# rx_path.net
KiCad netlist of a schematic drawn in Altium Designer
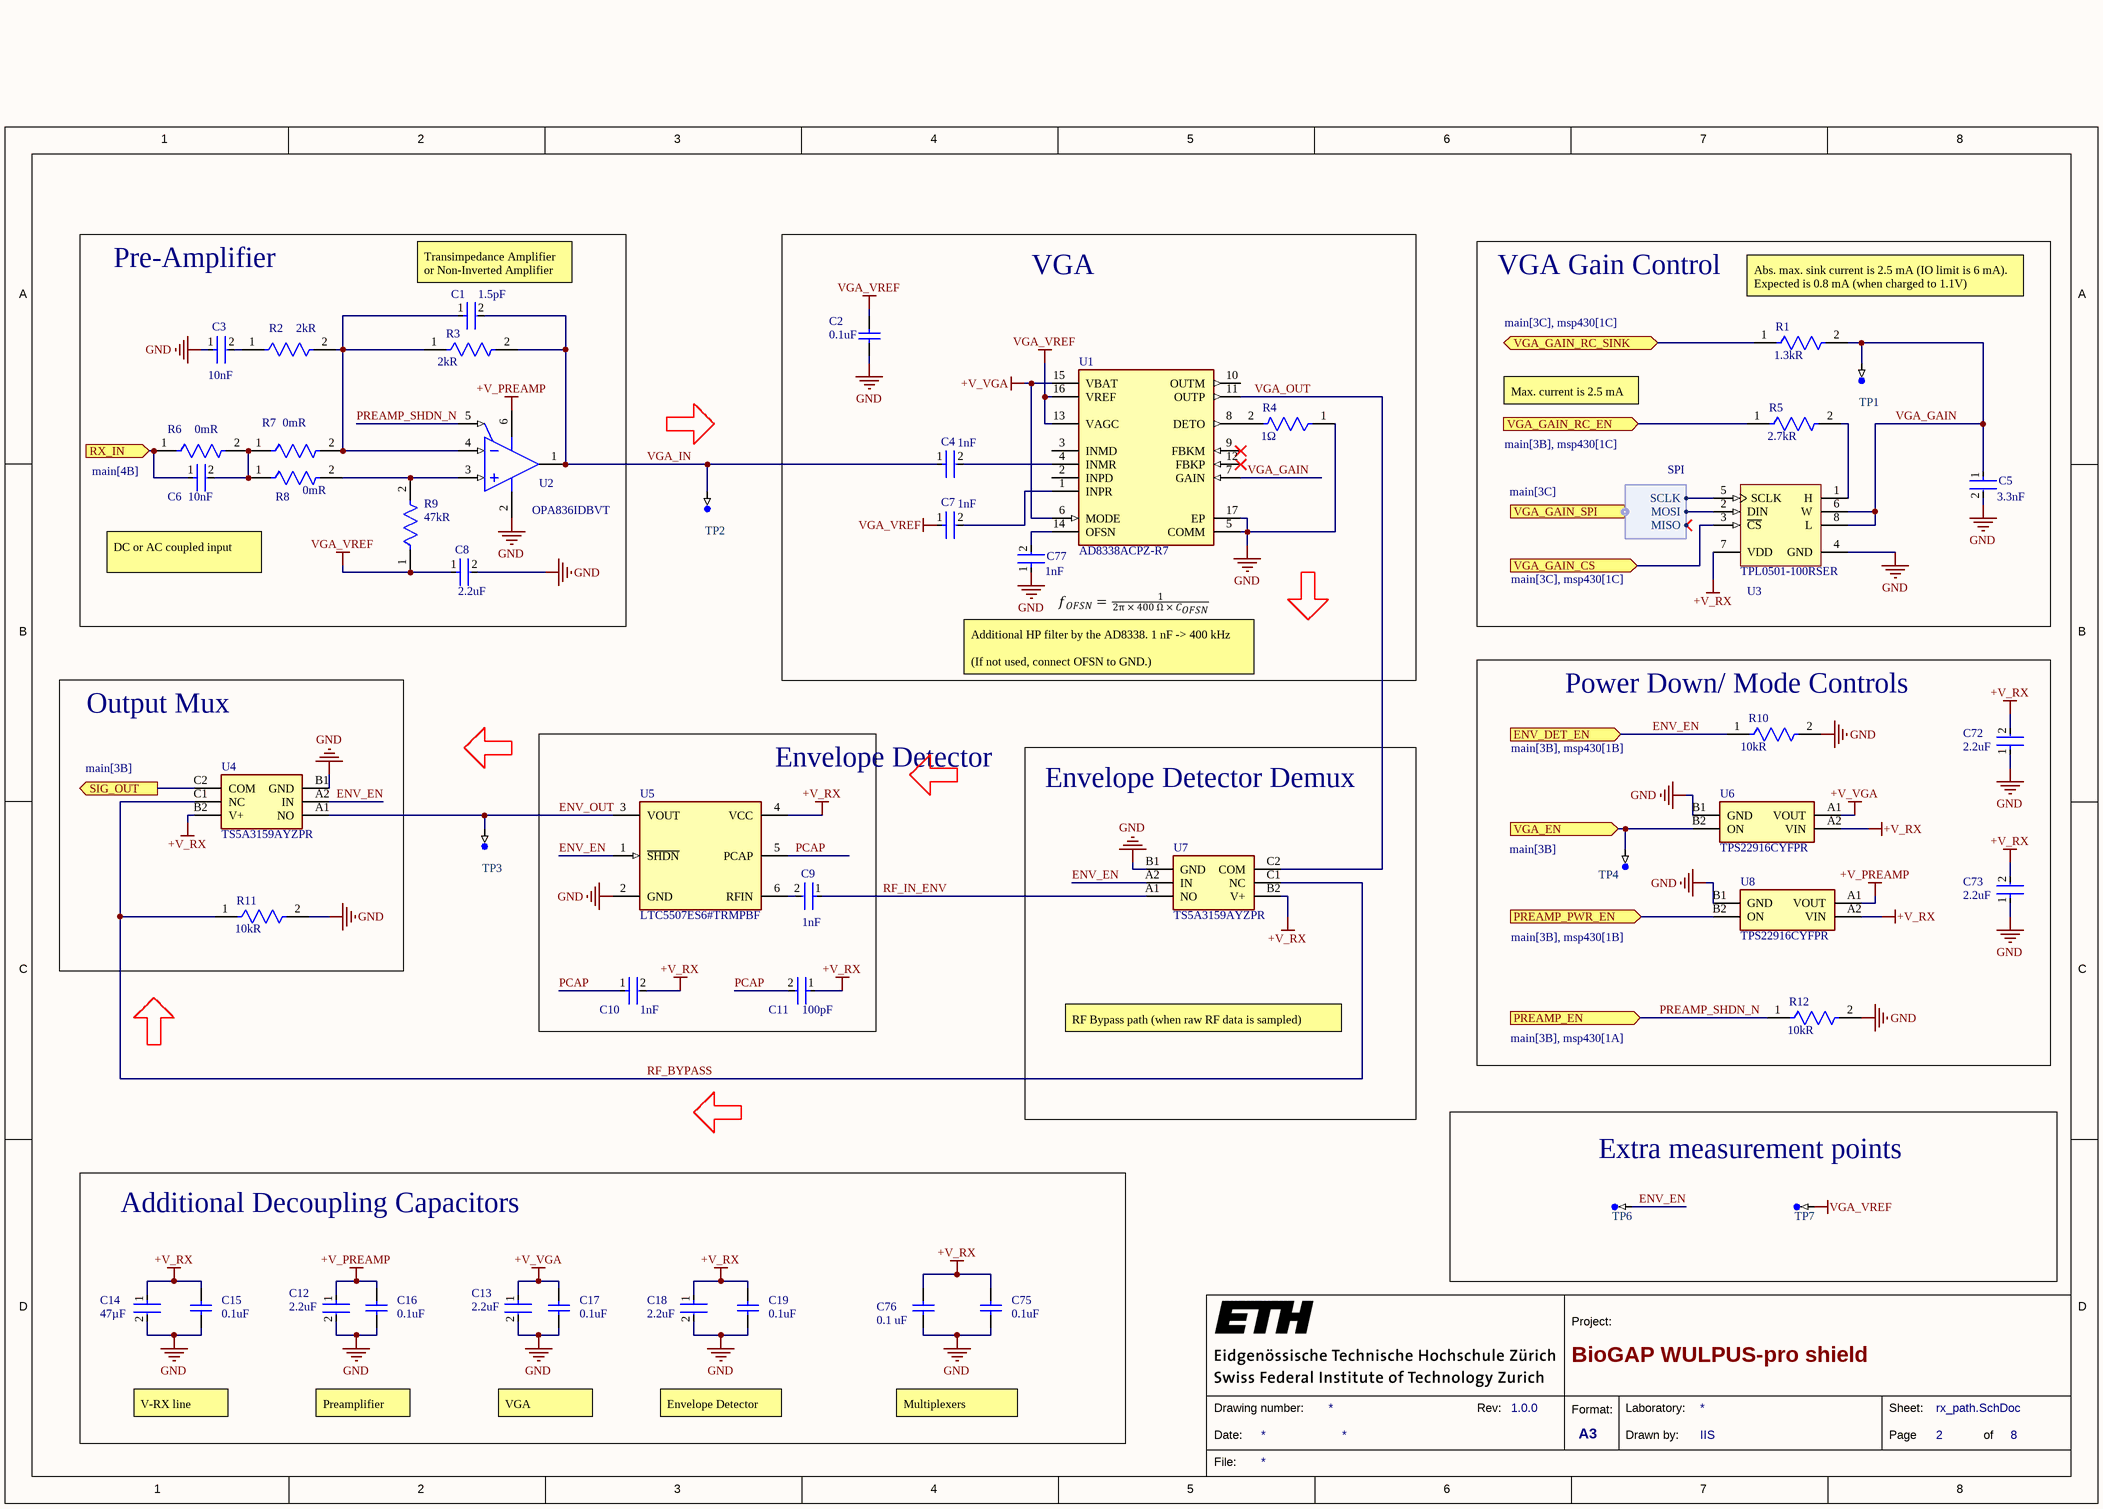
[diagram p0: rx_path.SchDoc]

(export (version "E")
  (design (tool "Eeschema 10.0.6"))
  (components
    (comp (ref "C1")
      (value "GJM1555C1H1R5BB01D")
      (footprint "FP-GJM155-0_05-IPC_C")
      (fields (field (name "CAPACITANCE") "1.5pF") (field (name "VOLTAGE") "50V"))
      (libsource (lib "Altium Content Vault") (part "02cd4be3c70576c341d710602a673aa"))
    )
    (comp (ref "C2")
      (value "C0402C104K4RACTU")
      (footprint "CAPC1005X55X30LL05T10")
      (fields (field (name "MANUFACTURER") "Kemet") (field (name "CAPACITANCE") "0.1uF"))
      (libsource (lib "Altium Content Vault") (part "CAP"))
    )
    (comp (ref "C3")
      (value "GRM033R71A103KA01D")
      (footprint "FP-GRM033-0_03-IPC_B")
      (fields
        (field (name "VOLTAGE") "10V")
        (field (name "CAPACITANCE") "10nF")
        (field (name "TOLERANCE") "10%")
      )
      (libsource (lib "Altium Content Vault") (part "b4654b650e69147ec39a6b967a45e02"))
    )
    (comp (ref "C4")
      (value "GRM1555C1H102JA01D")
      (footprint "FP-GRM155-0_05-IPC_B")
      (fields
        (field (name "TOLERANCE") "5%")
        (field (name "VOLTAGE") "50V")
        (field (name "CAPACITANCE") "1nF")
      )
      (libsource (lib "Altium Content Vault") (part "02cd4be3c70576c341d710602a673aa"))
    )
    (comp (ref "C5")
      (value "04025C332JAT2A")
      (footprint "FP-0402-L_1_0_1-W_0_5_0_1-IPC_C")
      (fields (field (name "CAPACITANCE") "3.3nF") (field (name "TOLERANCE") "5%"))
      (libsource (lib "Altium Content Vault") (part "b4654b650e69147ec39a6b967a45e02"))
    )
    (comp (ref "C6")
      (value "GRM033R71A103KA01D")
      (footprint "FP-GRM033-0_03-IPC_B")
      (fields
        (field (name "VOLTAGE") "10V")
        (field (name "CAPACITANCE") "10nF")
        (field (name "TOLERANCE") "10%")
      )
      (libsource (lib "Altium Content Vault") (part "b4654b650e69147ec39a6b967a45e02"))
    )
    (comp (ref "C7")
      (value "GRM1555C1H102JA01D")
      (footprint "FP-GRM155-0_05-IPC_B")
      (fields
        (field (name "TOLERANCE") "5%")
        (field (name "VOLTAGE") "50V")
        (field (name "CAPACITANCE") "1nF")
      )
      (libsource (lib "Altium Content Vault") (part "02cd4be3c70576c341d710602a673aa"))
    )
    (comp (ref "C8")
      (value "C1005X7S1A225K050BC")
      (footprint "FP-C1005-050-0_15-0_1-MFG")
      (fields (field (name "CAPACITANCE") "2.2uF") (field (name "TOLERANCE") "10%"))
      (libsource (lib "Altium Content Vault") (part "b4654b650e69147ec39a6b967a45e02"))
    )
    (comp (ref "C9")
      (value "GRM1555C1H102JA01D")
      (footprint "FP-GRM155-0_05-IPC_B")
      (fields
        (field (name "TOLERANCE") "5%")
        (field (name "VOLTAGE") "50V")
        (field (name "CAPACITANCE") "1nF")
      )
      (libsource (lib "Altium Content Vault") (part "02cd4be3c70576c341d710602a673aa"))
    )
    (comp (ref "C10")
      (value "GRM1555C1H102JA01D")
      (footprint "FP-GRM155-0_05-IPC_B")
      (fields
        (field (name "TOLERANCE") "5%")
        (field (name "VOLTAGE") "50V")
        (field (name "CAPACITANCE") "1nF")
      )
      (libsource (lib "Altium Content Vault") (part "02cd4be3c70576c341d710602a673aa"))
    )
    (comp (ref "C11")
      (value "04025A101FAT2A")
      (footprint "FP-0402-L_1_0_1-W_0_5_0_1-MFG")
      (fields
        (field (name "CAPACITANCE") "100pF")
        (field (name "VOLTAGE") "50V")
        (field (name "TOLERANCE") "1%")
      )
      (libsource (lib "Altium Content Vault") (part "b4654b650e69147ec39a6b967a45e02"))
    )
    (comp (ref "C12")
      (value "C1005X7S1A225K050BC")
      (footprint "FP-C1005-050-0_15-0_1-MFG")
      (fields (field (name "CAPACITANCE") "2.2uF") (field (name "TOLERANCE") "10%"))
      (libsource (lib "Altium Content Vault") (part "b4654b650e69147ec39a6b967a45e02"))
    )
    (comp (ref "C13")
      (value "C1005X7S1A225K050BC")
      (footprint "FP-C1005-050-0_15-0_1-MFG")
      (fields (field (name "CAPACITANCE") "2.2uF") (field (name "TOLERANCE") "10%"))
      (libsource (lib "Altium Content Vault") (part "b4654b650e69147ec39a6b967a45e02"))
    )
    (comp (ref "C14")
      (value "GRM188R60J476ME01D")
      (footprint "FP-GRM188-0_2-MFG")
      (fields (field (name "TOLERANCE") "20%") (field (name "CAPACITANCE") "47µF"))
      (libsource (lib "Altium Content Vault") (part "b4654b650e69147ec39a6b967a45e02"))
    )
    (comp (ref "C15")
      (value "C0402C104K4RACTU")
      (footprint "CAPC1005X55X30LL05T10")
      (fields (field (name "MANUFACTURER") "Kemet") (field (name "CAPACITANCE") "0.1uF"))
      (libsource (lib "Altium Content Vault") (part "CAP"))
    )
    (comp (ref "C16")
      (value "C0402C104K4RACTU")
      (footprint "CAPC1005X55X30LL05T10")
      (fields (field (name "MANUFACTURER") "Kemet") (field (name "CAPACITANCE") "0.1uF"))
      (libsource (lib "Altium Content Vault") (part "CAP"))
    )
    (comp (ref "C17")
      (value "C0402C104K4RACTU")
      (footprint "CAPC1005X55X30LL05T10")
      (fields (field (name "MANUFACTURER") "Kemet") (field (name "CAPACITANCE") "0.1uF"))
      (libsource (lib "Altium Content Vault") (part "CAP"))
    )
    (comp (ref "C18")
      (value "C1005X7S1A225K050BC")
      (footprint "FP-C1005-050-0_15-0_1-MFG")
      (fields (field (name "CAPACITANCE") "2.2uF") (field (name "TOLERANCE") "10%"))
      (libsource (lib "Altium Content Vault") (part "b4654b650e69147ec39a6b967a45e02"))
    )
    (comp (ref "C19")
      (value "C0402C104K4RACTU")
      (footprint "CAPC1005X55X30LL05T10")
      (fields (field (name "MANUFACTURER") "Kemet") (field (name "CAPACITANCE") "0.1uF"))
      (libsource (lib "Altium Content Vault") (part "CAP"))
    )
    (comp (ref "C72")
      (value "C1005X7S1A225K050BC")
      (footprint "FP-C1005-050-0_15-0_1-MFG")
      (fields (field (name "CAPACITANCE") "2.2uF") (field (name "TOLERANCE") "10%"))
      (libsource (lib "Altium Content Vault") (part "b4654b650e69147ec39a6b967a45e02"))
    )
    (comp (ref "C73")
      (value "C1005X7S1A225K050BC")
      (footprint "FP-C1005-050-0_15-0_1-MFG")
      (fields (field (name "CAPACITANCE") "2.2uF") (field (name "TOLERANCE") "10%"))
      (libsource (lib "Altium Content Vault") (part "b4654b650e69147ec39a6b967a45e02"))
    )
    (comp (ref "C75")
      (value "C0402C104K4RACTU")
      (footprint "CAPC1005X55X30LL05T10")
      (fields (field (name "MANUFACTURER") "Kemet") (field (name "CAPACITANCE") "0.1uF"))
      (libsource (lib "Altium Content Vault") (part "CAP"))
    )
    (comp (ref "C76")
      (value "C0402C104K4RACTU")
      (footprint "CAPC1005X55X30LL05T10")
      (fields (field (name "MANUFACTURER") "Kemet") (field (name "CAPACITANCE") "0.1 uF"))
      (libsource (lib "Altium Content Vault") (part "CAP"))
    )
    (comp (ref "C77")
      (value "GRM1555C1H102JA01D")
      (footprint "FP-GRM155-0_05-IPC_B")
      (fields
        (field (name "TOLERANCE") "5%")
        (field (name "VOLTAGE") "50V")
        (field (name "CAPACITANCE") "1nF")
      )
      (libsource (lib "Altium Content Vault") (part "02cd4be3c70576c341d710602a673aa"))
    )
    (comp (ref "R1")
      (value "CRCW04021K30JNED")
      (footprint "FP-CRCW0402-e3-IPC_B")
      (fields (field (name "TOLERANCE") "5%") (field (name "RESISTANCE") "1.3kR"))
      (libsource (lib "Altium Content Vault") (part "1029c3af85768c4190bb7ad29bc67b5"))
    )
    (comp (ref "R2")
      (value "ERJ-2RKF2001X")
      (footprint "FP-ERJ2RK-MFG")
      (fields (field (name "RESISTANCE") "2kR") (field (name "TOLERANCE") "1%"))
      (libsource (lib "Altium Content Vault") (part "1029c3af85768c4190bb7ad29bc67b5"))
    )
    (comp (ref "R3")
      (value "ERJ-2RKF2001X")
      (footprint "FP-ERJ2RK-MFG")
      (fields (field (name "RESISTANCE") "2kR") (field (name "TOLERANCE") "1%"))
      (libsource (lib "Altium Content Vault") (part "1029c3af85768c4190bb7ad29bc67b5"))
    )
    (comp (ref "R4")
      (value "CRCW04021R00FKEDC")
      (footprint "FP-CRCW0402-C-e3-MFG")
      (fields (field (name "RESISTANCE") "1Ω") (field (name "TOLERANCE") "1%"))
      (libsource (lib "Altium Content Vault") (part "1029c3af85768c4190bb7ad29bc67b5"))
    )
    (comp (ref "R5")
      (value "MCS04020C2701FE000")
      (footprint "FP-MCS0402-IPC_B")
      (fields (field (name "RESISTANCE") "2.7kR") (field (name "TOLERANCE") "1%"))
      (libsource (lib "Altium Content Vault") (part "1029c3af85768c4190bb7ad29bc67b5"))
    )
    (comp (ref "R6")
      (value "CRCW04020000Z0ED")
      (footprint "FP-CRCW0402-e3-IPC_C")
      (fields (field (name "TOLERANCE") "5%") (field (name "RESISTANCE") "0mR"))
      (libsource (lib "Altium Content Vault") (part "1029c3af85768c4190bb7ad29bc67b5"))
    )
    (comp (ref "R7")
      (value "CRCW04020000Z0ED")
      (footprint "FP-CRCW0402-e3-IPC_C")
      (fields (field (name "TOLERANCE") "5%") (field (name "RESISTANCE") "0mR"))
      (libsource (lib "Altium Content Vault") (part "1029c3af85768c4190bb7ad29bc67b5"))
    )
    (comp (ref "R8")
      (value "CRCW04020000Z0ED")
      (footprint "FP-CRCW0402-e3-IPC_C")
      (fields (field (name "TOLERANCE") "5%") (field (name "RESISTANCE") "0mR"))
      (libsource (lib "Altium Content Vault") (part "1029c3af85768c4190bb7ad29bc67b5"))
    )
    (comp (ref "R9")
      (value "RMCF0201JT47K0")
      (footprint "FP-RMCF0201-MFG")
      (fields (field (name "RESISTANCE") "47kR") (field (name "TOLERANCE") "5%"))
      (libsource (lib "Altium Content Vault") (part "1029c3af85768c4190bb7ad29bc67b5"))
    )
    (comp (ref "R10")
      (value "CRCW040210K0JNED")
      (footprint "FP-CRCW0402-e3-IPC_B")
      (fields (field (name "RESISTANCE") "10kR") (field (name "TOLERANCE") "5%"))
      (libsource (lib "Altium Content Vault") (part "1029c3af85768c4190bb7ad29bc67b5"))
    )
    (comp (ref "R11")
      (value "CRCW040210K0JNED")
      (footprint "FP-CRCW0402-e3-IPC_B")
      (fields (field (name "RESISTANCE") "10kR") (field (name "TOLERANCE") "5%"))
      (libsource (lib "Altium Content Vault") (part "1029c3af85768c4190bb7ad29bc67b5"))
    )
    (comp (ref "R12")
      (value "CRCW040210K0JNED")
      (footprint "FP-CRCW0402-e3-IPC_B")
      (fields (field (name "RESISTANCE") "10kR") (field (name "TOLERANCE") "5%"))
      (libsource (lib "Altium Content Vault") (part "1029c3af85768c4190bb7ad29bc67b5"))
    )
    (comp (ref "TP1")
      (value "TP-SM-C-100")
      (footprint "TP-SM-C-100")
      (description "Test Point, Surface Mount, Circular, Pad Diameter 1 mm")
      (libsource (lib "wulpus") (part "CMP-0484-00002-1"))
    )
    (comp (ref "TP2")
      (value "TP-SM-C-100")
      (footprint "TP-SM-C-100")
      (description "Test Point, Surface Mount, Circular, Pad Diameter 1 mm")
      (libsource (lib "wulpus") (part "CMP-0484-00002-1"))
    )
    (comp (ref "TP3")
      (value "TP-SM-C-100")
      (footprint "TP-SM-C-100")
      (description "Test Point, Surface Mount, Circular, Pad Diameter 1 mm")
      (libsource (lib "wulpus") (part "CMP-0484-00002-1"))
    )
    (comp (ref "TP4")
      (value "TP-SM-C-100")
      (footprint "TP-SM-C-100")
      (description "Test Point, Surface Mount, Circular, Pad Diameter 1 mm")
      (libsource (lib "wulpus") (part "CMP-0484-00002-1"))
    )
    (comp (ref "TP6")
      (value "TP-SM-C-100")
      (footprint "TP-SM-C-100")
      (description "Test Point, Surface Mount, Circular, Pad Diameter 1 mm")
      (libsource (lib "wulpus") (part "CMP-0484-00002-1"))
    )
    (comp (ref "TP7")
      (value "TP-SM-C-100")
      (footprint "TP-SM-C-100")
      (description "Test Point, Surface Mount, Circular, Pad Diameter 1 mm")
      (libsource (lib "wulpus") (part "CMP-0484-00002-1"))
    )
    (comp (ref "U1")
      (value "AD8338ACPZ-R7")
      (footprint "FP-CP-16-22-IPC_C")
      (description "IC OPAMP VGA 1 CIRCUIT 16LFCSP")
      (fields
        (field (name "OCTOPART") "https://octopart.com/ad8338acpz-r7-analog+devices-21054770")
        (field (name "MANUFACTURER") "Analog Devices")
      )
      (libsource (lib "Altium Content Vault") (part "4ce7887af0b7713ffabab50ab6d8fb3"))
    )
    (comp (ref "U2")
      (value "OPA836IDBVT")
      (footprint "DBV0006A_L")
      (fields (field (name "MANUFACTURER") "Texas Instruments"))
      (libsource (lib "wulpus") (part "CMP-0018-00480-2"))
    )
    (comp (ref "U3")
      (value "TPL0501-100RSER")
      (footprint "TI-RSE8_V")
      (fields (field (name "MANUFACTURER") "Texas Instruments"))
      (libsource (lib "Altium Content Vault") (part "TI-TPL0501-100RSE8"))
    )
    (comp (ref "U4")
      (value "TS5A3159AYZPR")
      (footprint "BGA6C50P2X3_89X139X50")
      (description "Analogue Switch ICs SPDT ANALOG SWITCH")
      (libsource (lib "TS5A3159AYZPR") (part "TS5A3159AYZPR"))
    )
    (comp (ref "U5")
      (value "LTC5507ES6#TRMPBF")
      (footprint "FP-LTC5507ES6#TRMPBF-IPC_B")
      (description "IC RF DETECT 100KHZ-1GHZ TSOT23")
      (fields
        (field (name "OCTOPART") "https://octopart.com/ltc5507es6%23trmpbf-analog+devices-88320008")
        (field (name "MANUFACTURER") "Analog Devices")
      )
      (libsource (lib "Altium Content Vault") (part "942e158bd38935f4e9b1d9ad82e87f8"))
    )
    (comp (ref "U6")
      (value "TPS22916CYFPR")
      (footprint "BGA4C40P2X2_78X78X50")
      (description "TPS22916 5.5-V, 2-A Ultra-Low Leakage Load Switch")
      (libsource (lib "TPS22916CYFPR") (part "TPS22916CYFPR"))
    )
    (comp (ref "U7")
      (value "TS5A3159AYZPR")
      (footprint "BGA6C50P2X3_89X139X50")
      (description "Analogue Switch ICs SPDT ANALOG SWITCH")
      (libsource (lib "") (part "TS5A3159AYZPR_1"))
    )
    (comp (ref "U8")
      (value "TPS22916CYFPR")
      (footprint "BGA4C40P2X2_78X78X50")
      (description "TPS22916 5.5-V, 2-A Ultra-Low Leakage Load Switch")
      (libsource (lib "TPS22916CYFPR") (part "TPS22916CYFPR"))
    )
  )
  (nets
    (net (code "2") (name "+V_PREAMP") (class "Default")
      (node (ref "C12") (pin "1") (pinfunction "1_1") (pintype "passive"))
      (node (ref "C16") (pin "2") (pinfunction "2_2") (pintype "passive"))
      (node (ref "U2") (pin "6") (pinfunction "VS+_6") (pintype "power_in"))
      (node (ref "U8") (pin "A1") (pinfunction "VOUT_A1") (pintype "passive"))
    )
    (net (code "3") (name "+V_RX") (class "Default")
      (node (ref "C10") (pin "2") (pinfunction "2_2") (pintype "passive"))
      (node (ref "C11") (pin "1") (pinfunction "1_1") (pintype "passive"))
      (node (ref "C14") (pin "1") (pinfunction "1_1") (pintype "passive"))
      (node (ref "C15") (pin "2") (pinfunction "2_2") (pintype "passive"))
      (node (ref "C18") (pin "1") (pinfunction "1_1") (pintype "passive"))
      (node (ref "C19") (pin "2") (pinfunction "2_2") (pintype "passive"))
      (node (ref "C72") (pin "2") (pinfunction "2_2") (pintype "passive"))
      (node (ref "C73") (pin "2") (pinfunction "2_2") (pintype "passive"))
      (node (ref "C75") (pin "2") (pinfunction "2_2") (pintype "passive"))
      (node (ref "C76") (pin "2") (pinfunction "2_2") (pintype "passive"))
      (node (ref "U3") (pin "7") (pinfunction "VDD_7") (pintype "power_in"))
      (node (ref "U4") (pin "B2") (pinfunction "V+_B2") (pintype "passive"))
      (node (ref "U5") (pin "4") (pinfunction "VCC_4") (pintype "power_in"))
      (node (ref "U6") (pin "A2") (pinfunction "VIN_A2") (pintype "passive"))
      (node (ref "U7") (pin "B2") (pinfunction "V+_B2") (pintype "passive"))
      (node (ref "U8") (pin "A2") (pinfunction "VIN_A2") (pintype "passive"))
    )
    (net (code "4") (name "+V_VGA") (class "Default")
      (node (ref "C13") (pin "1") (pinfunction "1_1") (pintype "passive"))
      (node (ref "C17") (pin "2") (pinfunction "2_2") (pintype "passive"))
      (node (ref "U1") (pin "15") (pinfunction "VBAT_15") (pintype "power_in"))
      (node (ref "U1") (pin "6") (pinfunction "MODE_6") (pintype "input"))
      (node (ref "U6") (pin "A1") (pinfunction "VOUT_A1") (pintype "passive"))
    )
    (net (code "5") (name "/ENV_EN") (class "Default")
      (node (ref "R10") (pin "1") (pinfunction "1_1") (pintype "passive"))
      (node (ref "TP6") (pin "1") (pinfunction "1_1") (pintype "input"))
      (node (ref "U4") (pin "A2") (pinfunction "IN_A2") (pintype "passive"))
      (node (ref "U5") (pin "1") (pinfunction "~{SHDN}_1") (pintype "input"))
      (node (ref "U7") (pin "A2") (pinfunction "IN_A2") (pintype "passive"))
    )
    (net (code "6") (name "/ENV_OUT") (class "Default")
      (node (ref "TP3") (pin "1") (pinfunction "1_1") (pintype "input"))
      (node (ref "U4") (pin "A1") (pinfunction "NO_A1") (pintype "passive"))
      (node (ref "U5") (pin "3") (pinfunction "VOUT_3") (pintype "passive"))
    )
    (net (code "7") (name "/MOSI") (class "Default")
      (node (ref "U3") (pin "2") (pinfunction "DIN_2") (pintype "input"))
    )
    (net (code "8") (name "/PCAP") (class "Default")
      (node (ref "C10") (pin "1") (pinfunction "1_1") (pintype "passive"))
      (node (ref "C11") (pin "2") (pinfunction "2_2") (pintype "passive"))
      (node (ref "U5") (pin "5") (pinfunction "PCAP_5") (pintype "passive"))
    )
    (net (code "9") (name "/PREAMP_PWR_EN") (class "Default")
      (node (ref "U8") (pin "B2") (pinfunction "ON_B2") (pintype "passive"))
    )
    (net (code "10") (name "/PREAMP_SHDN_N") (class "Default")
      (node (ref "R12") (pin "1") (pinfunction "1_1") (pintype "passive"))
      (node (ref "U2") (pin "5") (pinfunction "~{PD}_5") (pintype "input"))
    )
    (net (code "11") (name "/RF_BYPASS") (class "Default")
      (node (ref "R11") (pin "1") (pinfunction "1_1") (pintype "passive"))
      (node (ref "U4") (pin "C1") (pinfunction "NC_C1") (pintype "passive"))
      (node (ref "U7") (pin "C1") (pinfunction "NC_C1") (pintype "passive"))
    )
    (net (code "12") (name "/RF_IN_ENV") (class "Default")
      (node (ref "C9") (pin "1") (pinfunction "1_1") (pintype "passive"))
      (node (ref "U7") (pin "A1") (pinfunction "NO_A1") (pintype "passive"))
    )
    (net (code "13") (name "/RX_IN") (class "Default")
      (node (ref "C6") (pin "1") (pinfunction "1_1") (pintype "passive"))
      (node (ref "R6") (pin "1") (pinfunction "1_1") (pintype "passive"))
    )
    (net (code "14") (name "/SCLK") (class "Default")
      (node (ref "U3") (pin "5") (pinfunction "SCLK_5") (pintype "input"))
    )
    (net (code "15") (name "/SIG_OUT") (class "Default")
      (node (ref "U4") (pin "C2") (pinfunction "COM_C2") (pintype "passive"))
    )
    (net (code "16") (name "/VGA_EN") (class "Default")
      (node (ref "TP4") (pin "1") (pinfunction "1_1") (pintype "input"))
      (node (ref "U6") (pin "B2") (pinfunction "ON_B2") (pintype "passive"))
    )
    (net (code "17") (name "/VGA_GAIN") (class "Default")
      (node (ref "C5") (pin "1") (pinfunction "1_1") (pintype "passive"))
      (node (ref "R1") (pin "2") (pinfunction "2_2") (pintype "passive"))
      (node (ref "TP1") (pin "1") (pinfunction "1_1") (pintype "input"))
      (node (ref "U1") (pin "7") (pinfunction "GAIN_7") (pintype "input"))
      (node (ref "U3") (pin "6") (pinfunction "W_6") (pintype "passive"))
      (node (ref "U3") (pin "8") (pinfunction "L_8") (pintype "passive"))
    )
    (net (code "18") (name "/VGA_GAIN_CS") (class "Default")
      (node (ref "U3") (pin "3") (pinfunction "~{CS}_3") (pintype "input"))
    )
    (net (code "19") (name "/VGA_GAIN_RC_EN") (class "Default")
      (node (ref "R5") (pin "1") (pinfunction "1_1") (pintype "passive"))
    )
    (net (code "20") (name "/VGA_GAIN_RC_SINK") (class "Default")
      (node (ref "R1") (pin "1") (pinfunction "1_1") (pintype "passive"))
    )
    (net (code "21") (name "/VGA_IN") (class "Default")
      (node (ref "C1") (pin "2") (pinfunction "2_2") (pintype "passive"))
      (node (ref "C4") (pin "1") (pinfunction "1_1") (pintype "passive"))
      (node (ref "R3") (pin "2") (pinfunction "2_2") (pintype "passive"))
      (node (ref "TP2") (pin "1") (pinfunction "1_1") (pintype "input"))
      (node (ref "U2") (pin "1") (pinfunction "VOUT_1") (pintype "tri_state"))
    )
    (net (code "22") (name "/VGA_OUT") (class "Default")
      (node (ref "U1") (pin "11") (pinfunction "OUTP_11") (pintype "output"))
      (node (ref "U7") (pin "C2") (pinfunction "COM_C2") (pintype "passive"))
    )
    (net (code "24") (name "GND") (class "Default")
      (node (ref "C12") (pin "2") (pinfunction "2_2") (pintype "passive"))
      (node (ref "C13") (pin "2") (pinfunction "2_2") (pintype "passive"))
      (node (ref "C14") (pin "2") (pinfunction "2_2") (pintype "passive"))
      (node (ref "C15") (pin "1") (pinfunction "1_1") (pintype "passive"))
      (node (ref "C16") (pin "1") (pinfunction "1_1") (pintype "passive"))
      (node (ref "C17") (pin "1") (pinfunction "1_1") (pintype "passive"))
      (node (ref "C18") (pin "2") (pinfunction "2_2") (pintype "passive"))
      (node (ref "C19") (pin "1") (pinfunction "1_1") (pintype "passive"))
      (node (ref "C2") (pin "1") (pinfunction "1_1") (pintype "passive"))
      (node (ref "C3") (pin "1") (pinfunction "1_1") (pintype "passive"))
      (node (ref "C5") (pin "2") (pinfunction "2_2") (pintype "passive"))
      (node (ref "C72") (pin "1") (pinfunction "1_1") (pintype "passive"))
      (node (ref "C73") (pin "1") (pinfunction "1_1") (pintype "passive"))
      (node (ref "C75") (pin "1") (pinfunction "1_1") (pintype "passive"))
      (node (ref "C76") (pin "1") (pinfunction "1_1") (pintype "passive"))
      (node (ref "C77") (pin "1") (pinfunction "1_1") (pintype "passive"))
      (node (ref "C8") (pin "2") (pinfunction "2_2") (pintype "passive"))
      (node (ref "R10") (pin "2") (pinfunction "2_2") (pintype "passive"))
      (node (ref "R11") (pin "2") (pinfunction "2_2") (pintype "passive"))
      (node (ref "R12") (pin "2") (pinfunction "2_2") (pintype "passive"))
      (node (ref "R4") (pin "1") (pinfunction "1_1") (pintype "passive"))
      (node (ref "U1") (pin "17") (pinfunction "EP_17") (pintype "power_in"))
      (node (ref "U1") (pin "5") (pinfunction "COMM_5") (pintype "power_in"))
      (node (ref "U2") (pin "2") (pinfunction "VS-_2") (pintype "power_in"))
      (node (ref "U3") (pin "4") (pinfunction "GND_4") (pintype "power_in"))
      (node (ref "U4") (pin "B1") (pinfunction "GND_B1") (pintype "passive"))
      (node (ref "U5") (pin "2") (pinfunction "GND_2") (pintype "power_in"))
      (node (ref "U6") (pin "B1") (pinfunction "GND_B1") (pintype "passive"))
      (node (ref "U7") (pin "B1") (pinfunction "GND_B1") (pintype "passive"))
      (node (ref "U8") (pin "B1") (pinfunction "GND_B1") (pintype "passive"))
    )
    (net (code "25") (name "Net-(C3-Pad2)") (class "Default")
      (node (ref "C3") (pin "2") (pinfunction "2_2") (pintype "passive"))
      (node (ref "R2") (pin "1") (pinfunction "1_1") (pintype "passive"))
    )
    (net (code "26") (name "Net-(C6-Pad2)") (class "Default")
      (node (ref "C6") (pin "2") (pinfunction "2_2") (pintype "passive"))
      (node (ref "R6") (pin "2") (pinfunction "2_2") (pintype "passive"))
      (node (ref "R7") (pin "1") (pinfunction "1_1") (pintype "passive"))
      (node (ref "R8") (pin "1") (pinfunction "1_1") (pintype "passive"))
    )
    (net (code "27") (name "Net-(U1-DETO)") (class "Default")
      (node (ref "R4") (pin "2") (pinfunction "2_2") (pintype "passive"))
      (node (ref "U1") (pin "8") (pinfunction "DETO_8") (pintype "output"))
    )
    (net (code "28") (name "Net-(U1-INMR)") (class "Default")
      (node (ref "C4") (pin "2") (pinfunction "2_2") (pintype "passive"))
      (node (ref "U1") (pin "4") (pinfunction "INMR_4") (pintype "passive"))
    )
    (net (code "29") (name "Net-(U1-INPR)") (class "Default")
      (node (ref "C7") (pin "2") (pinfunction "2_2") (pintype "passive"))
      (node (ref "U1") (pin "1") (pinfunction "INPR_1") (pintype "passive"))
    )
    (net (code "30") (name "Net-(U1-OFSN)") (class "Default")
      (node (ref "C77") (pin "2") (pinfunction "2_2") (pintype "passive"))
      (node (ref "U1") (pin "14") (pinfunction "OFSN_14") (pintype "passive"))
    )
    (net (code "31") (name "Net-(U2-VIN+)") (class "Default")
      (node (ref "R8") (pin "2") (pinfunction "2_2") (pintype "passive"))
      (node (ref "R9") (pin "2") (pinfunction "2_2") (pintype "passive"))
      (node (ref "U2") (pin "3") (pinfunction "VIN+_3") (pintype "input"))
    )
    (net (code "32") (name "Net-(U2-VIN-)") (class "Default")
      (node (ref "C1") (pin "1") (pinfunction "1_1") (pintype "passive"))
      (node (ref "R2") (pin "2") (pinfunction "2_2") (pintype "passive"))
      (node (ref "R3") (pin "1") (pinfunction "1_1") (pintype "passive"))
      (node (ref "R7") (pin "2") (pinfunction "2_2") (pintype "passive"))
      (node (ref "U2") (pin "4") (pinfunction "VIN-_4") (pintype "input"))
    )
    (net (code "33") (name "Net-(U3-H)") (class "Default")
      (node (ref "R5") (pin "2") (pinfunction "2_2") (pintype "passive"))
      (node (ref "U3") (pin "1") (pinfunction "H_1") (pintype "passive"))
    )
    (net (code "34") (name "Net-(U5-RFIN)") (class "Default")
      (node (ref "C9") (pin "2") (pinfunction "2_2") (pintype "passive"))
      (node (ref "U5") (pin "6") (pinfunction "RFIN_6") (pintype "passive"))
    )
    (net (code "35") (name "VGA_VREF") (class "Default")
      (node (ref "C2") (pin "2") (pinfunction "2_2") (pintype "passive"))
      (node (ref "C7") (pin "1") (pinfunction "1_1") (pintype "passive"))
      (node (ref "C8") (pin "1") (pinfunction "1_1") (pintype "passive"))
      (node (ref "R9") (pin "1") (pinfunction "1_1") (pintype "passive"))
      (node (ref "TP7") (pin "1") (pinfunction "1_1") (pintype "input"))
      (node (ref "U1") (pin "13") (pinfunction "VAGC_13") (pintype "power_in"))
      (node (ref "U1") (pin "16") (pinfunction "VREF_16") (pintype "power_in"))
    )
    (net (code "36") (name "unconnected-(U1-FBKM-Pad9)") (class "Default")
      (node (ref "U1") (pin "9") (pinfunction "FBKM_9") (pintype "input+no_connect"))
    )
    (net (code "37") (name "unconnected-(U1-FBKP-Pad12)") (class "Default")
      (node (ref "U1") (pin "12") (pinfunction "FBKP_12") (pintype "input+no_connect"))
    )
    (net (code "38") (name "unconnected-(U1-INMD-Pad3)") (class "Default")
      (node (ref "U1") (pin "3") (pinfunction "INMD_3") (pintype "passive"))
    )
    (net (code "39") (name "unconnected-(U1-INPD-Pad2)") (class "Default")
      (node (ref "U1") (pin "2") (pinfunction "INPD_2") (pintype "passive"))
    )
    (net (code "40") (name "unconnected-(U1-OUTM-Pad10)") (class "Default")
      (node (ref "U1") (pin "10") (pinfunction "OUTM_10") (pintype "output"))
    )
  )
)
